# Sensor_Acquisition_Board_Rear_rev2.net
KiCad netlist of a schematic drawn in EAGLE
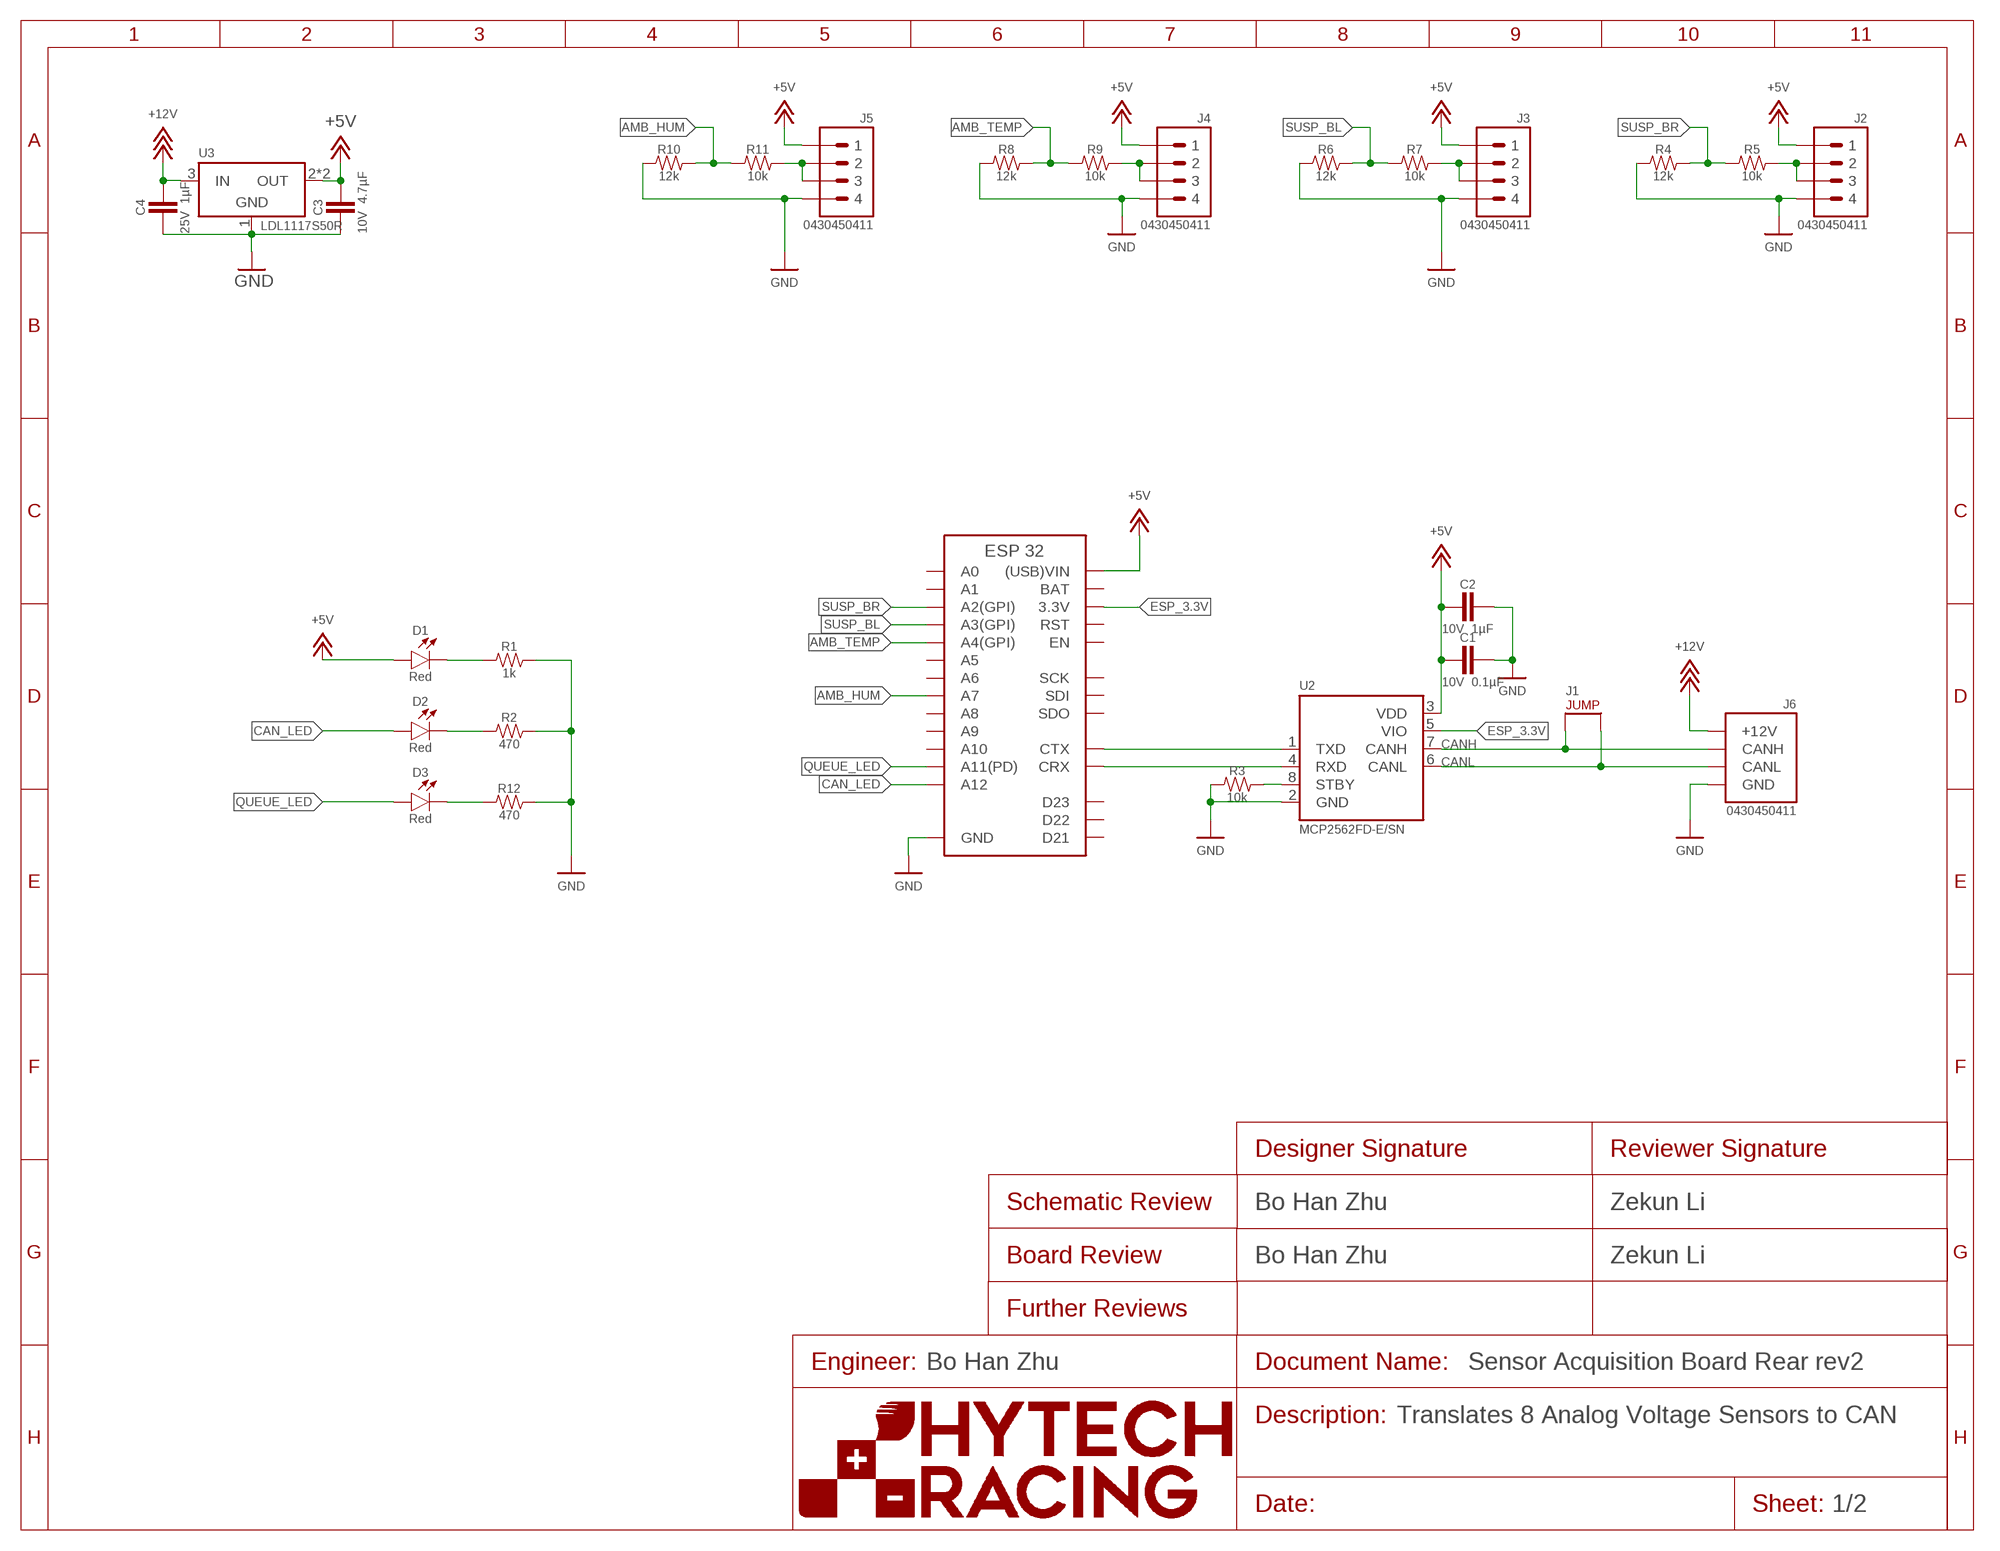
[diagram p0: schematic, sheet 1]
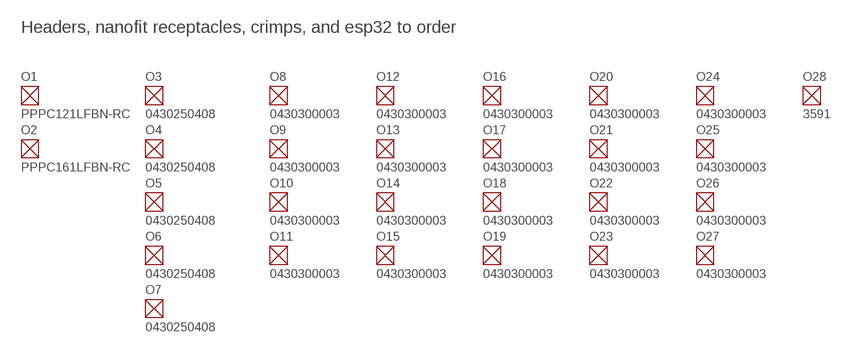
[diagram p1: schematic, sheet 2]

(export (version "E")
  (design (tool "Eeschema 10.0.6"))
  (components
    (comp (ref "A2")
      (value "ESP32")
      (footprint "eagle-import:ESP32")
      (libsource (lib "eagle-import") (part "ESP32"))
    )
    (comp (ref "C1")
      (value "CAPACITOR_0603_10V_0.1UF")
      (footprint "eagle-import:0603-CAP")
      (fields
        (field (name "CAPACITANCE") "0.1µF")
        (field (name "MANUFACTURER") "Vishay Vitramon")
        (field (name "MPN") "VJ0603Y104JXQPW1BC")
        (field (name "TOLERANCE") "5%")
        (field (name "VOLTAGE") "10V")
      )
      (libsource (lib "eagle-import") (part "CAPACITOR_?_060310V_0.1UF"))
    )
    (comp (ref "C2")
      (value "CAPACITOR_0603_10V_1UF")
      (footprint "eagle-import:0603-CAP")
      (fields
        (field (name "CAPACITANCE") "1µF")
        (field (name "MANUFACTURER") "Yageo")
        (field (name "MPN") "CC0603KRX7R6BB105")
        (field (name "TOLERANCE") "10%")
        (field (name "VOLTAGE") "10V")
      )
      (libsource (lib "eagle-import") (part "CAPACITOR_?_060310V_1UF"))
    )
    (comp (ref "C3")
      (value "CAPACITOR_0603_10V_4.7UF")
      (footprint "eagle-import:0603-CAP")
      (fields
        (field (name "CAPACITANCE") "4.7µF")
        (field (name "MANUFACTURER") "Samsung Electro-Mechanics")
        (field (name "MPN") "CL10A475KP8NNNC")
        (field (name "TOLERANCE") "10%")
        (field (name "VOLTAGE") "10V")
      )
      (libsource (lib "eagle-import") (part "CAPACITOR_?_060310V_4.7UF"))
    )
    (comp (ref "C4")
      (value "CAPACITOR_0603_25V_1UF")
      (footprint "eagle-import:0603-CAP")
      (fields
        (field (name "CAPACITANCE") "1µF")
        (field (name "MANUFACTURER") "Samsung Electro-Mechanics")
        (field (name "MPN") "CL10B105KA8NNNC")
        (field (name "TOLERANCE") "10%")
        (field (name "VOLTAGE") "25V")
      )
      (libsource (lib "eagle-import") (part "CAPACITOR_?_060325V_1UF"))
    )
    (comp (ref "D1")
      (value "LED_0603_RED")
      (footprint "eagle-import:0603-LED")
      (fields
        (field (name "COLOR") "Red")
        (field (name "MANUFACTURER") "Kingbright")
        (field (name "MPN") "APT1608SECK/J3-PRV")
      )
      (libsource (lib "eagle-import") (part "LED_?_0603RED"))
    )
    (comp (ref "D2")
      (value "LED_0603_RED")
      (footprint "eagle-import:0603-LED")
      (fields
        (field (name "COLOR") "Red")
        (field (name "MANUFACTURER") "Kingbright")
        (field (name "MPN") "APT1608SECK/J3-PRV")
      )
      (libsource (lib "eagle-import") (part "LED_?_0603RED"))
    )
    (comp (ref "D3")
      (value "LED_0603_RED")
      (footprint "eagle-import:0603-LED")
      (fields
        (field (name "COLOR") "Red")
        (field (name "MANUFACTURER") "Kingbright")
        (field (name "MPN") "APT1608SECK/J3-PRV")
      )
      (libsource (lib "eagle-import") (part "LED_?_0603RED"))
    )
    (comp (ref "J1")
      (value "JUMPER_0603_")
      (footprint "eagle-import:0603-RES")
      (fields (field (name "MPN") "RC0603FR-130RL") (field (name "MANUFACTURER") "YAGEO"))
      (libsource (lib "eagle-import") (part "JUMPER_?_0603"))
    )
    (comp (ref "J2")
      (value "CONNECTOR-4_μF_S_RA_")
      (footprint "eagle-import:MOLEX_MICROFIT_SMD_RIGHTANGLE_04_DUAL")
      (fields (field (name "MPN") "0430450411") (field (name "MANUFACTURER") "Molex"))
      (libsource (lib "eagle-import") (part "CONNECTOR-4_?_μF_S_RA"))
    )
    (comp (ref "J3")
      (value "CONNECTOR-4_μF_S_RA_")
      (footprint "eagle-import:MOLEX_MICROFIT_SMD_RIGHTANGLE_04_DUAL")
      (fields (field (name "MPN") "0430450411") (field (name "MANUFACTURER") "Molex"))
      (libsource (lib "eagle-import") (part "CONNECTOR-4_?_μF_S_RA"))
    )
    (comp (ref "J4")
      (value "CONNECTOR-4_μF_S_RA_")
      (footprint "eagle-import:MOLEX_MICROFIT_SMD_RIGHTANGLE_04_DUAL")
      (fields (field (name "MPN") "0430450411") (field (name "MANUFACTURER") "Molex"))
      (libsource (lib "eagle-import") (part "CONNECTOR-4_?_μF_S_RA"))
    )
    (comp (ref "J5")
      (value "CONNECTOR-4_μF_S_RA_")
      (footprint "eagle-import:MOLEX_MICROFIT_SMD_RIGHTANGLE_04_DUAL")
      (fields (field (name "MPN") "0430450411") (field (name "MANUFACTURER") "Molex"))
      (libsource (lib "eagle-import") (part "CONNECTOR-4_?_μF_S_RA"))
    )
    (comp (ref "J6")
      (value "CONNECTOR-CAN_μF_S_RA_")
      (footprint "eagle-import:MOLEX_MICROFIT_SMD_RIGHTANGLE_04_DUAL")
      (fields (field (name "MPN") "0430450411") (field (name "MANUFACTURER") "Molex"))
      (libsource (lib "eagle-import") (part "CONNECTOR-CAN_?_μF_S_RA"))
    )
    (comp (ref "R1")
      (value "RESISTOR_0603_1K")
      (footprint "eagle-import:0603-RES")
      (fields
        (field (name "MANUFACTURER") "Yageo")
        (field (name "MPN") "RC0603FR-071KL")
        (field (name "POWER") "0.1W")
        (field (name "RESISTANCE") "1k")
      )
      (libsource (lib "eagle-import") (part "RESISTOR_?_06031K"))
    )
    (comp (ref "R2")
      (value "RESISTOR_0603_470")
      (footprint "eagle-import:0603-RES")
      (fields
        (field (name "MANUFACTURER") "Panasonic Electronic Components")
        (field (name "MPN") "ERJ-PA3F4700V")
        (field (name "POWER") "0.25W")
        (field (name "RESISTANCE") "470")
      )
      (libsource (lib "eagle-import") (part "RESISTOR_?_0603470"))
    )
    (comp (ref "R3")
      (value "RESISTOR_0603_10K")
      (footprint "eagle-import:0603-RES")
      (fields
        (field (name "MANUFACTURER") "Yageo")
        (field (name "MPN") "RC0603FR-0710KL")
        (field (name "POWER") "0.1W")
        (field (name "RESISTANCE") "10k")
      )
      (libsource (lib "eagle-import") (part "RESISTOR_?_060310K"))
    )
    (comp (ref "R4")
      (value "RESISTOR_0603_12K")
      (footprint "eagle-import:0603-RES")
      (fields
        (field (name "MANUFACTURER") "Yageo")
        (field (name "MPN") "RC0603FR-0712KL")
        (field (name "POWER") "0.1W")
        (field (name "RESISTANCE") "12k")
      )
      (libsource (lib "eagle-import") (part "RESISTOR_?_060312K"))
    )
    (comp (ref "R5")
      (value "RESISTOR_0603_10K")
      (footprint "eagle-import:0603-RES")
      (fields
        (field (name "MANUFACTURER") "Yageo")
        (field (name "MPN") "RC0603FR-0710KL")
        (field (name "POWER") "0.1W")
        (field (name "RESISTANCE") "10k")
      )
      (libsource (lib "eagle-import") (part "RESISTOR_?_060310K"))
    )
    (comp (ref "R6")
      (value "RESISTOR_0603_12K")
      (footprint "eagle-import:0603-RES")
      (fields
        (field (name "MANUFACTURER") "Yageo")
        (field (name "MPN") "RC0603FR-0712KL")
        (field (name "POWER") "0.1W")
        (field (name "RESISTANCE") "12k")
      )
      (libsource (lib "eagle-import") (part "RESISTOR_?_060312K"))
    )
    (comp (ref "R7")
      (value "RESISTOR_0603_10K")
      (footprint "eagle-import:0603-RES")
      (fields
        (field (name "MANUFACTURER") "Yageo")
        (field (name "MPN") "RC0603FR-0710KL")
        (field (name "POWER") "0.1W")
        (field (name "RESISTANCE") "10k")
      )
      (libsource (lib "eagle-import") (part "RESISTOR_?_060310K"))
    )
    (comp (ref "R8")
      (value "RESISTOR_0603_12K")
      (footprint "eagle-import:0603-RES")
      (fields
        (field (name "MANUFACTURER") "Yageo")
        (field (name "MPN") "RC0603FR-0712KL")
        (field (name "POWER") "0.1W")
        (field (name "RESISTANCE") "12k")
      )
      (libsource (lib "eagle-import") (part "RESISTOR_?_060312K"))
    )
    (comp (ref "R9")
      (value "RESISTOR_0603_10K")
      (footprint "eagle-import:0603-RES")
      (fields
        (field (name "MANUFACTURER") "Yageo")
        (field (name "MPN") "RC0603FR-0710KL")
        (field (name "POWER") "0.1W")
        (field (name "RESISTANCE") "10k")
      )
      (libsource (lib "eagle-import") (part "RESISTOR_?_060310K"))
    )
    (comp (ref "R10")
      (value "RESISTOR_0603_12K")
      (footprint "eagle-import:0603-RES")
      (fields
        (field (name "MANUFACTURER") "Yageo")
        (field (name "MPN") "RC0603FR-0712KL")
        (field (name "POWER") "0.1W")
        (field (name "RESISTANCE") "12k")
      )
      (libsource (lib "eagle-import") (part "RESISTOR_?_060312K"))
    )
    (comp (ref "R11")
      (value "RESISTOR_0603_10K")
      (footprint "eagle-import:0603-RES")
      (fields
        (field (name "MANUFACTURER") "Yageo")
        (field (name "MPN") "RC0603FR-0710KL")
        (field (name "POWER") "0.1W")
        (field (name "RESISTANCE") "10k")
      )
      (libsource (lib "eagle-import") (part "RESISTOR_?_060310K"))
    )
    (comp (ref "R12")
      (value "RESISTOR_0603_470")
      (footprint "eagle-import:0603-RES")
      (fields
        (field (name "MANUFACTURER") "Panasonic Electronic Components")
        (field (name "MPN") "ERJ-PA3F4700V")
        (field (name "POWER") "0.25W")
        (field (name "RESISTANCE") "470")
      )
      (libsource (lib "eagle-import") (part "RESISTOR_?_0603470"))
    )
    (comp (ref "U2")
      (value "MCP2562FD")
      (footprint "eagle-import:SOIC-08(NARROW,0.15_)")
      (fields (field (name "MPN") "MCP2562FD-E/SN") (field (name "MANUFACTURER") "Microchip Technology"))
      (libsource (lib "eagle-import") (part "MCP2562FD"))
    )
    (comp (ref "U3")
      (value "VOLTAGE_REGULATOR_SOT-223_5V")
      (footprint "eagle-import:SOT-223")
      (fields (field (name "MANUFACTURER") "STMicroelectronics") (field (name "MPN") "LDL1117S50R"))
      (libsource (lib "eagle-import") (part "VOLTAGE_REGULATOR_?_SOT-2235V"))
    )
  )
  (nets
    (net (code "1") (name "+5V") (class "Default")
      (node (ref "A2") (pin "USB") (pinfunction "(USB)VIN_USB") (pintype "power_in"))
      (node (ref "C1") (pin "2") (pinfunction "2_2") (pintype "passive"))
      (node (ref "C2") (pin "2") (pinfunction "2_2") (pintype "passive"))
      (node (ref "C3") (pin "1") (pinfunction "1_1") (pintype "passive"))
      (node (ref "D1") (pin "2") (pinfunction "A_2") (pintype "passive"))
      (node (ref "J2") (pin "1") (pinfunction "1_1") (pintype "passive"))
      (node (ref "J3") (pin "1") (pinfunction "1_1") (pintype "passive"))
      (node (ref "J4") (pin "1") (pinfunction "1_1") (pintype "passive"))
      (node (ref "J5") (pin "1") (pinfunction "1_1") (pintype "passive"))
      (node (ref "U2") (pin "3") (pinfunction "VDD_3") (pintype "power_in"))
      (node (ref "U3") (pin "2") (pinfunction "OUT_2") (pintype "power_in"))
      (node (ref "U3") (pin "4") (pinfunction "OUT_4") (pintype "power_in"))
    )
    (net (code "2") (name "+12V") (class "Default")
      (node (ref "C4") (pin "1") (pinfunction "1_1") (pintype "passive"))
      (node (ref "J6") (pin "1") (pinfunction "+12V_1") (pintype "power_in"))
      (node (ref "U3") (pin "3") (pinfunction "IN_3") (pintype "power_in"))
    )
    (net (code "3") (name "AMB_HUM") (class "Default")
      (node (ref "A2") (pin "D32") (pinfunction "A7_D32") (pintype "bidirectional"))
      (node (ref "R10") (pin "2") (pinfunction "2_2") (pintype "passive"))
      (node (ref "R11") (pin "1") (pinfunction "1_1") (pintype "passive"))
    )
    (net (code "4") (name "AMB_TEMP") (class "Default")
      (node (ref "A2") (pin "A4") (pinfunction "A4(GPI)_A4") (pintype "bidirectional"))
      (node (ref "R8") (pin "2") (pinfunction "2_2") (pintype "passive"))
      (node (ref "R9") (pin "1") (pinfunction "1_1") (pintype "passive"))
    )
    (net (code "5") (name "BAT") (class "Default")
      (node (ref "A2") (pin "BAT") (pinfunction "BAT_BAT") (pintype "power_in"))
    )
    (net (code "6") (name "CANH") (class "Default")
      (node (ref "J1") (pin "1") (pinfunction "1_1") (pintype "passive"))
      (node (ref "J6") (pin "4") (pinfunction "CANH_4") (pintype "bidirectional"))
      (node (ref "U2") (pin "7") (pinfunction "CANH_7") (pintype "bidirectional"))
    )
    (net (code "7") (name "CANL") (class "Default")
      (node (ref "J1") (pin "2") (pinfunction "2_2") (pintype "passive"))
      (node (ref "J6") (pin "3") (pinfunction "CANL_3") (pintype "bidirectional"))
      (node (ref "U2") (pin "6") (pinfunction "CANL_6") (pintype "bidirectional"))
    )
    (net (code "8") (name "CAN_LED") (class "Default")
      (node (ref "A2") (pin "D13") (pinfunction "A12_D13") (pintype "bidirectional"))
      (node (ref "D2") (pin "2") (pinfunction "A_2") (pintype "passive"))
    )
    (net (code "9") (name "EN") (class "Default")
      (node (ref "A2") (pin "EN") (pinfunction "EN_EN") (pintype "power_in"))
    )
    (net (code "10") (name "ESP_3.3V") (class "Default")
      (node (ref "A2") (pin "3.3V") (pinfunction "3.3V_3.3V") (pintype "power_in"))
      (node (ref "U2") (pin "5") (pinfunction "VIO_5") (pintype "power_in"))
    )
    (net (code "11") (name "GND") (class "Default")
      (node (ref "A2") (pin "GND") (pinfunction "GND_GND") (pintype "power_in"))
      (node (ref "C1") (pin "1") (pinfunction "1_1") (pintype "passive"))
      (node (ref "C2") (pin "1") (pinfunction "1_1") (pintype "passive"))
      (node (ref "C3") (pin "2") (pinfunction "2_2") (pintype "passive"))
      (node (ref "C4") (pin "2") (pinfunction "2_2") (pintype "passive"))
      (node (ref "J2") (pin "4") (pinfunction "4_4") (pintype "passive"))
      (node (ref "J3") (pin "4") (pinfunction "4_4") (pintype "passive"))
      (node (ref "J4") (pin "4") (pinfunction "4_4") (pintype "passive"))
      (node (ref "J5") (pin "4") (pinfunction "4_4") (pintype "passive"))
      (node (ref "J6") (pin "2") (pinfunction "GND_2") (pintype "power_in"))
      (node (ref "R1") (pin "2") (pinfunction "2_2") (pintype "passive"))
      (node (ref "R10") (pin "1") (pinfunction "1_1") (pintype "passive"))
      (node (ref "R12") (pin "2") (pinfunction "2_2") (pintype "passive"))
      (node (ref "R2") (pin "2") (pinfunction "2_2") (pintype "passive"))
      (node (ref "R3") (pin "1") (pinfunction "1_1") (pintype "passive"))
      (node (ref "R4") (pin "1") (pinfunction "1_1") (pintype "passive"))
      (node (ref "R6") (pin "1") (pinfunction "1_1") (pintype "passive"))
      (node (ref "R8") (pin "1") (pinfunction "1_1") (pintype "passive"))
      (node (ref "U2") (pin "2") (pinfunction "GND_2") (pintype "power_in"))
      (node (ref "U3") (pin "1") (pinfunction "GND_1") (pintype "power_in"))
    )
    (net (code "12") (name "Net-(A2-CRX)") (class "Default")
      (node (ref "A2") (pin "RX") (pinfunction "CRX_RX") (pintype "bidirectional"))
      (node (ref "U2") (pin "4") (pinfunction "RXD_4") (pintype "output"))
    )
    (net (code "13") (name "Net-(A2-CTX)") (class "Default")
      (node (ref "A2") (pin "TX") (pinfunction "CTX_TX") (pintype "bidirectional"))
      (node (ref "U2") (pin "1") (pinfunction "TXD_1") (pintype "input"))
    )
    (net (code "14") (name "Net-(D1-C)") (class "Default")
      (node (ref "D1") (pin "1") (pinfunction "C_1") (pintype "passive"))
      (node (ref "R1") (pin "1") (pinfunction "1_1") (pintype "passive"))
    )
    (net (code "15") (name "Net-(D2-C)") (class "Default")
      (node (ref "D2") (pin "1") (pinfunction "C_1") (pintype "passive"))
      (node (ref "R2") (pin "1") (pinfunction "1_1") (pintype "passive"))
    )
    (net (code "16") (name "Net-(D3-C)") (class "Default")
      (node (ref "D3") (pin "1") (pinfunction "C_1") (pintype "passive"))
      (node (ref "R12") (pin "1") (pinfunction "1_1") (pintype "passive"))
    )
    (net (code "17") (name "Net-(J2-Pad2)") (class "Default")
      (node (ref "J2") (pin "2") (pinfunction "2_2") (pintype "passive"))
      (node (ref "J2") (pin "3") (pinfunction "3_3") (pintype "passive"))
      (node (ref "R5") (pin "2") (pinfunction "2_2") (pintype "passive"))
    )
    (net (code "18") (name "Net-(J3-Pad2)") (class "Default")
      (node (ref "J3") (pin "2") (pinfunction "2_2") (pintype "passive"))
      (node (ref "J3") (pin "3") (pinfunction "3_3") (pintype "passive"))
      (node (ref "R7") (pin "2") (pinfunction "2_2") (pintype "passive"))
    )
    (net (code "19") (name "Net-(J4-Pad2)") (class "Default")
      (node (ref "J4") (pin "2") (pinfunction "2_2") (pintype "passive"))
      (node (ref "J4") (pin "3") (pinfunction "3_3") (pintype "passive"))
      (node (ref "R9") (pin "2") (pinfunction "2_2") (pintype "passive"))
    )
    (net (code "20") (name "Net-(J5-Pad2)") (class "Default")
      (node (ref "J5") (pin "2") (pinfunction "2_2") (pintype "passive"))
      (node (ref "J5") (pin "3") (pinfunction "3_3") (pintype "passive"))
      (node (ref "R11") (pin "2") (pinfunction "2_2") (pintype "passive"))
    )
    (net (code "21") (name "Net-(U2-STBY)") (class "Default")
      (node (ref "R3") (pin "2") (pinfunction "2_2") (pintype "passive"))
      (node (ref "U2") (pin "8") (pinfunction "STBY_8") (pintype "passive"))
    )
    (net (code "22") (name "QUEUE_LED") (class "Default")
      (node (ref "A2") (pin "D12") (pinfunction "A11(PD)_D12") (pintype "bidirectional"))
      (node (ref "D3") (pin "2") (pinfunction "A_2") (pintype "passive"))
    )
    (net (code "23") (name "RST") (class "Default")
      (node (ref "A2") (pin "RST") (pinfunction "RST_RST") (pintype "power_in"))
    )
    (net (code "24") (name "SUSP_BL") (class "Default")
      (node (ref "A2") (pin "A3") (pinfunction "A3(GPI)_A3") (pintype "bidirectional"))
      (node (ref "R6") (pin "2") (pinfunction "2_2") (pintype "passive"))
      (node (ref "R7") (pin "1") (pinfunction "1_1") (pintype "passive"))
    )
    (net (code "25") (name "SUSP_BR") (class "Default")
      (node (ref "A2") (pin "A2") (pinfunction "A2(GPI)_A2") (pintype "bidirectional"))
      (node (ref "R4") (pin "2") (pinfunction "2_2") (pintype "passive"))
      (node (ref "R5") (pin "1") (pinfunction "1_1") (pintype "passive"))
    )
    (net (code "26") (name "unconnected-(A2-A6-PadD14)") (class "Default")
      (node (ref "A2") (pin "D14") (pinfunction "A6_D14") (pintype "bidirectional"))
    )
    (net (code "27") (name "unconnected-(A2-A8-PadD15)") (class "Default")
      (node (ref "A2") (pin "D15") (pinfunction "A8_D15") (pintype "bidirectional"))
    )
    (net (code "28") (name "unconnected-(A2-A9-PadD33)") (class "Default")
      (node (ref "A2") (pin "D33") (pinfunction "A9_D33") (pintype "bidirectional"))
    )
    (net (code "29") (name "unconnected-(A2-A10-PadD27)") (class "Default")
      (node (ref "A2") (pin "D27") (pinfunction "A10_D27") (pintype "bidirectional"))
    )
    (net (code "30") (name "unconnected-(A2-D22-PadSDA)") (class "Default")
      (node (ref "A2") (pin "SDA") (pinfunction "D22_SDA") (pintype "bidirectional"))
    )
    (net (code "31") (name "unconnected-(A2-D23-PadSCL)") (class "Default")
      (node (ref "A2") (pin "SCL") (pinfunction "D23_SCL") (pintype "bidirectional"))
    )
    (net (code "32") (name "unconnected-(A2-PadA0)") (class "Default")
      (node (ref "A2") (pin "A0") (pinfunction "A0_A0") (pintype "bidirectional"))
    )
    (net (code "33") (name "unconnected-(A2-PadA1)") (class "Default")
      (node (ref "A2") (pin "A1") (pinfunction "A1_A1") (pintype "bidirectional"))
    )
    (net (code "34") (name "unconnected-(A2-PadA5)") (class "Default")
      (node (ref "A2") (pin "A5") (pinfunction "A5_A5") (pintype "bidirectional"))
    )
    (net (code "35") (name "unconnected-(A2-PadD21)") (class "Default")
      (node (ref "A2") (pin "D21") (pinfunction "D21_D21") (pintype "bidirectional"))
    )
    (net (code "36") (name "unconnected-(A2-PadSCK)") (class "Default")
      (node (ref "A2") (pin "SCK") (pinfunction "SCK_SCK") (pintype "bidirectional"))
    )
    (net (code "37") (name "unconnected-(A2-SDI-PadCIPO)") (class "Default")
      (node (ref "A2") (pin "CIPO") (pinfunction "SDI_CIPO") (pintype "bidirectional"))
    )
    (net (code "38") (name "unconnected-(A2-SDO-PadCOPI)") (class "Default")
      (node (ref "A2") (pin "COPI") (pinfunction "SDO_COPI") (pintype "bidirectional"))
    )
  )
)
